# PAM8320_Amplifier_Board_R2.net
KiCad netlist of a schematic drawn in EAGLE
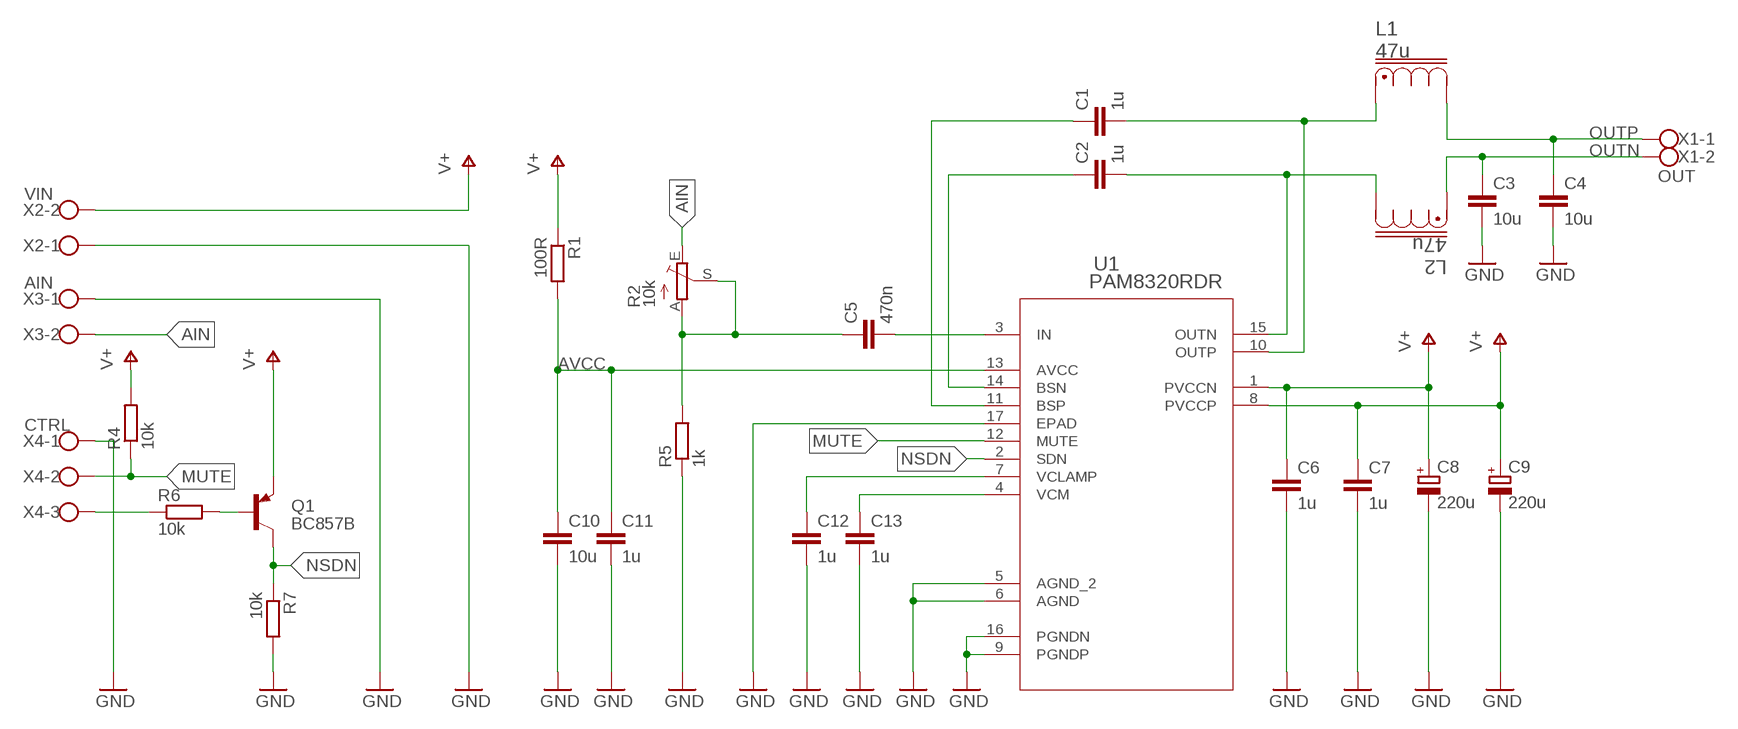
[diagram p0: schematic, sheet 1]

(export (version "E")
  (design (tool "Eeschema 10.0.6"))
  (components
    (comp (ref "C1")
      (value "1u")
      (footprint "eagle-import:C0805")
      (libsource (lib "eagle-import") (part "C-EUC0805"))
    )
    (comp (ref "C2")
      (value "1u")
      (footprint "eagle-import:C0805")
      (libsource (lib "eagle-import") (part "C-EUC0805"))
    )
    (comp (ref "C3")
      (value "10u")
      (footprint "eagle-import:C1206")
      (libsource (lib "eagle-import") (part "C-EUC1206"))
    )
    (comp (ref "C4")
      (value "10u")
      (footprint "eagle-import:C1206")
      (libsource (lib "eagle-import") (part "C-EUC1206"))
    )
    (comp (ref "C5")
      (value "470n")
      (footprint "eagle-import:C1206")
      (libsource (lib "eagle-import") (part "C-EUC1206"))
    )
    (comp (ref "C6")
      (value "1u")
      (footprint "eagle-import:C0805")
      (libsource (lib "eagle-import") (part "C-EUC0805"))
    )
    (comp (ref "C7")
      (value "1u")
      (footprint "eagle-import:C0805")
      (libsource (lib "eagle-import") (part "C-EUC0805"))
    )
    (comp (ref "C8")
      (value "220u")
      (footprint "eagle-import:UD-10X10_NICHICON")
      (libsource (lib "eagle-import") (part "CPOL-EUUD-10X10"))
    )
    (comp (ref "C9")
      (value "220u")
      (footprint "eagle-import:UD-10X10_NICHICON")
      (libsource (lib "eagle-import") (part "CPOL-EUUD-10X10"))
    )
    (comp (ref "C10")
      (value "10u")
      (footprint "eagle-import:C1206")
      (libsource (lib "eagle-import") (part "C-EUC1206"))
    )
    (comp (ref "C11")
      (value "1u")
      (footprint "eagle-import:C0805")
      (libsource (lib "eagle-import") (part "C-EUC0805"))
    )
    (comp (ref "C12")
      (value "1u")
      (footprint "eagle-import:C0805")
      (libsource (lib "eagle-import") (part "C-EUC0805"))
    )
    (comp (ref "C13")
      (value "1u")
      (footprint "eagle-import:C0805")
      (libsource (lib "eagle-import") (part "C-EUC0805"))
    )
    (comp (ref "L1")
      (value "47u")
      (footprint "eagle-import:DR127")
      (fields
        (field (name "MANUFACTURER_PART_NUMBER") "DR127-470-R")
        (field (name "COPYRIGHT") "Copyright (C) 2023 Ultra Librarian. All rights reserved.")
      )
      (libsource (lib "eagle-import") (part "DR127-470-R"))
    )
    (comp (ref "L2")
      (value "47u")
      (footprint "eagle-import:DR127")
      (fields
        (field (name "MANUFACTURER_PART_NUMBER") "DR127-470-R")
        (field (name "COPYRIGHT") "Copyright (C) 2023 Ultra Librarian. All rights reserved.")
      )
      (libsource (lib "eagle-import") (part "DR127-470-R"))
    )
    (comp (ref "Q1")
      (value "BC857B")
      (footprint "eagle-import:SOT23-BEC")
      (libsource (lib "eagle-import") (part "BC857SMDB"))
    )
    (comp (ref "R1")
      (value "100R")
      (footprint "eagle-import:R0603")
      (libsource (lib "eagle-import") (part "R-EU_R0603"))
    )
    (comp (ref "R2")
      (value "10k")
      (footprint "eagle-import:RJ9W")
      (libsource (lib "eagle-import") (part "TRIM_EU-RJ9W"))
    )
    (comp (ref "R4")
      (value "10k")
      (footprint "eagle-import:R0603")
      (libsource (lib "eagle-import") (part "R-EU_R0603"))
    )
    (comp (ref "R5")
      (value "1k")
      (footprint "eagle-import:R0603")
      (libsource (lib "eagle-import") (part "R-EU_R0603"))
    )
    (comp (ref "R6")
      (value "10k")
      (footprint "eagle-import:R0603")
      (libsource (lib "eagle-import") (part "R-EU_R0603"))
    )
    (comp (ref "R7")
      (value "10k")
      (footprint "eagle-import:R0603")
      (libsource (lib "eagle-import") (part "R-EU_R0603"))
    )
    (comp (ref "U1")
      (value "PAM8320RDR")
      (footprint "eagle-import:SO-16EP_3P9X9P9_DIO")
      (fields (field (name "COPYRIGHT") "Copyright (C) 2023 Ultra Librarian. All rights reserved."))
      (libsource (lib "eagle-import") (part "PAM8320RDR"))
    )
    (comp (ref "X1")
      (value "OUT")
      (footprint "eagle-import:W237-102")
      (fields (field (name "MPN") "237-102"))
      (libsource (lib "eagle-import") (part "W237-102"))
    )
    (comp (ref "X2")
      (value "VIN")
      (footprint "eagle-import:W237-102")
      (fields (field (name "MPN") "237-102"))
      (libsource (lib "eagle-import") (part "W237-102"))
    )
    (comp (ref "X3")
      (value "AIN")
      (footprint "eagle-import:W237-102")
      (fields (field (name "MPN") "237-102"))
      (libsource (lib "eagle-import") (part "W237-102"))
    )
    (comp (ref "X4")
      (value "CTRL")
      (footprint "eagle-import:W237-103")
      (fields (field (name "MPN") "237-103"))
      (libsource (lib "eagle-import") (part "W237-103"))
    )
  )
  (nets
    (net (code "1") (name "/AVCC") (class "Default")
      (node (ref "C10") (pin "1") (pinfunction "1_1") (pintype "passive"))
      (node (ref "C11") (pin "1") (pinfunction "1_1") (pintype "passive"))
      (node (ref "R1") (pin "2") (pinfunction "2_2") (pintype "passive"))
      (node (ref "U1") (pin "13") (pinfunction "AVCC_13") (pintype "passive"))
    )
    (net (code "2") (name "/OUTN") (class "Default")
      (node (ref "C3") (pin "1") (pinfunction "1_1") (pintype "passive"))
      (node (ref "L2") (pin "1") (pinfunction "1_1") (pintype "passive"))
      (node (ref "X1") (pin "2") (pinfunction "KL_2") (pintype "passive"))
    )
    (net (code "3") (name "/OUTP") (class "Default")
      (node (ref "C4") (pin "1") (pinfunction "1_1") (pintype "passive"))
      (node (ref "L1") (pin "2") (pinfunction "2_2") (pintype "passive"))
      (node (ref "X1") (pin "1") (pinfunction "KL_1") (pintype "passive"))
    )
    (net (code "4") (name "AIN") (class "Default")
      (node (ref "R2") (pin "E") (pinfunction "E_E") (pintype "passive"))
      (node (ref "X3") (pin "2") (pinfunction "KL_2") (pintype "passive"))
    )
    (net (code "5") (name "GND") (class "Default")
      (node (ref "C10") (pin "2") (pinfunction "2_2") (pintype "passive"))
      (node (ref "C11") (pin "2") (pinfunction "2_2") (pintype "passive"))
      (node (ref "C12") (pin "2") (pinfunction "2_2") (pintype "passive"))
      (node (ref "C13") (pin "2") (pinfunction "2_2") (pintype "passive"))
      (node (ref "C3") (pin "2") (pinfunction "2_2") (pintype "passive"))
      (node (ref "C4") (pin "2") (pinfunction "2_2") (pintype "passive"))
      (node (ref "C6") (pin "2") (pinfunction "2_2") (pintype "passive"))
      (node (ref "C7") (pin "2") (pinfunction "2_2") (pintype "passive"))
      (node (ref "C8") (pin "-") (pinfunction "-_-") (pintype "passive"))
      (node (ref "C9") (pin "-") (pinfunction "-_-") (pintype "passive"))
      (node (ref "R5") (pin "1") (pinfunction "1_1") (pintype "passive"))
      (node (ref "R7") (pin "2") (pinfunction "2_2") (pintype "passive"))
      (node (ref "U1") (pin "16") (pinfunction "PGNDN_16") (pintype "passive"))
      (node (ref "U1") (pin "17") (pinfunction "EPAD_17") (pintype "passive"))
      (node (ref "U1") (pin "5") (pinfunction "AGND_2_5") (pintype "passive"))
      (node (ref "U1") (pin "6") (pinfunction "AGND_6") (pintype "passive"))
      (node (ref "U1") (pin "9") (pinfunction "PGNDP_9") (pintype "passive"))
      (node (ref "X2") (pin "1") (pinfunction "KL_1") (pintype "passive"))
      (node (ref "X3") (pin "1") (pinfunction "KL_1") (pintype "passive"))
      (node (ref "X4") (pin "1") (pinfunction "KL_1") (pintype "passive"))
    )
    (net (code "6") (name "MUTE") (class "Default")
      (node (ref "R4") (pin "1") (pinfunction "1_1") (pintype "passive"))
      (node (ref "U1") (pin "12") (pinfunction "MUTE_12") (pintype "passive"))
      (node (ref "X4") (pin "2") (pinfunction "KL_2") (pintype "passive"))
    )
    (net (code "7") (name "NSDN") (class "Default")
      (node (ref "Q1") (pin "C") (pinfunction "C_C") (pintype "passive"))
      (node (ref "R7") (pin "1") (pinfunction "1_1") (pintype "passive"))
      (node (ref "U1") (pin "2") (pinfunction "SDN_2") (pintype "passive"))
    )
    (net (code "8") (name "Net-(C5-Pad1)") (class "Default")
      (node (ref "C5") (pin "1") (pinfunction "1_1") (pintype "passive"))
      (node (ref "R2") (pin "A") (pinfunction "A_A") (pintype "passive"))
      (node (ref "R2") (pin "S") (pinfunction "S_S") (pintype "passive"))
      (node (ref "R5") (pin "2") (pinfunction "2_2") (pintype "passive"))
    )
    (net (code "9") (name "Net-(Q1-PadB)") (class "Default")
      (node (ref "Q1") (pin "B") (pinfunction "B_B") (pintype "passive"))
      (node (ref "R6") (pin "2") (pinfunction "2_2") (pintype "passive"))
    )
    (net (code "10") (name "Net-(U1-BSN)") (class "Default")
      (node (ref "C2") (pin "1") (pinfunction "1_1") (pintype "passive"))
      (node (ref "U1") (pin "14") (pinfunction "BSN_14") (pintype "passive"))
    )
    (net (code "11") (name "Net-(U1-BSP)") (class "Default")
      (node (ref "C1") (pin "1") (pinfunction "1_1") (pintype "passive"))
      (node (ref "U1") (pin "11") (pinfunction "BSP_11") (pintype "passive"))
    )
    (net (code "12") (name "Net-(U1-IN)") (class "Default")
      (node (ref "C5") (pin "2") (pinfunction "2_2") (pintype "passive"))
      (node (ref "U1") (pin "3") (pinfunction "IN_3") (pintype "passive"))
    )
    (net (code "13") (name "Net-(U1-OUTN)") (class "Default")
      (node (ref "C2") (pin "2") (pinfunction "2_2") (pintype "passive"))
      (node (ref "L2") (pin "2") (pinfunction "2_2") (pintype "passive"))
      (node (ref "U1") (pin "15") (pinfunction "OUTN_15") (pintype "output"))
    )
    (net (code "14") (name "Net-(U1-OUTP)") (class "Default")
      (node (ref "C1") (pin "2") (pinfunction "2_2") (pintype "passive"))
      (node (ref "L1") (pin "1") (pinfunction "1_1") (pintype "passive"))
      (node (ref "U1") (pin "10") (pinfunction "OUTP_10") (pintype "output"))
    )
    (net (code "15") (name "Net-(U1-VCLAMP)") (class "Default")
      (node (ref "C12") (pin "1") (pinfunction "1_1") (pintype "passive"))
      (node (ref "U1") (pin "7") (pinfunction "VCLAMP_7") (pintype "passive"))
    )
    (net (code "16") (name "Net-(U1-VCM)") (class "Default")
      (node (ref "C13") (pin "1") (pinfunction "1_1") (pintype "passive"))
      (node (ref "U1") (pin "4") (pinfunction "VCM_4") (pintype "passive"))
    )
    (net (code "17") (name "Net-(X4C-KL)") (class "Default")
      (node (ref "R6") (pin "1") (pinfunction "1_1") (pintype "passive"))
      (node (ref "X4") (pin "3") (pinfunction "KL_3") (pintype "passive"))
    )
    (net (code "18") (name "V+") (class "Default")
      (node (ref "C6") (pin "1") (pinfunction "1_1") (pintype "passive"))
      (node (ref "C7") (pin "1") (pinfunction "1_1") (pintype "passive"))
      (node (ref "C8") (pin "+") (pinfunction "+_+") (pintype "passive"))
      (node (ref "C9") (pin "+") (pinfunction "+_+") (pintype "passive"))
      (node (ref "Q1") (pin "E") (pinfunction "E_E") (pintype "passive"))
      (node (ref "R1") (pin "1") (pinfunction "1_1") (pintype "passive"))
      (node (ref "R4") (pin "2") (pinfunction "2_2") (pintype "passive"))
      (node (ref "U1") (pin "1") (pinfunction "PVCCN_1") (pintype "passive"))
      (node (ref "U1") (pin "8") (pinfunction "PVCCP_8") (pintype "passive"))
      (node (ref "X2") (pin "2") (pinfunction "KL_2") (pintype "passive"))
    )
  )
)
